# DDL_demo_board.net
KiCad netlist of a schematic drawn in EAGLE
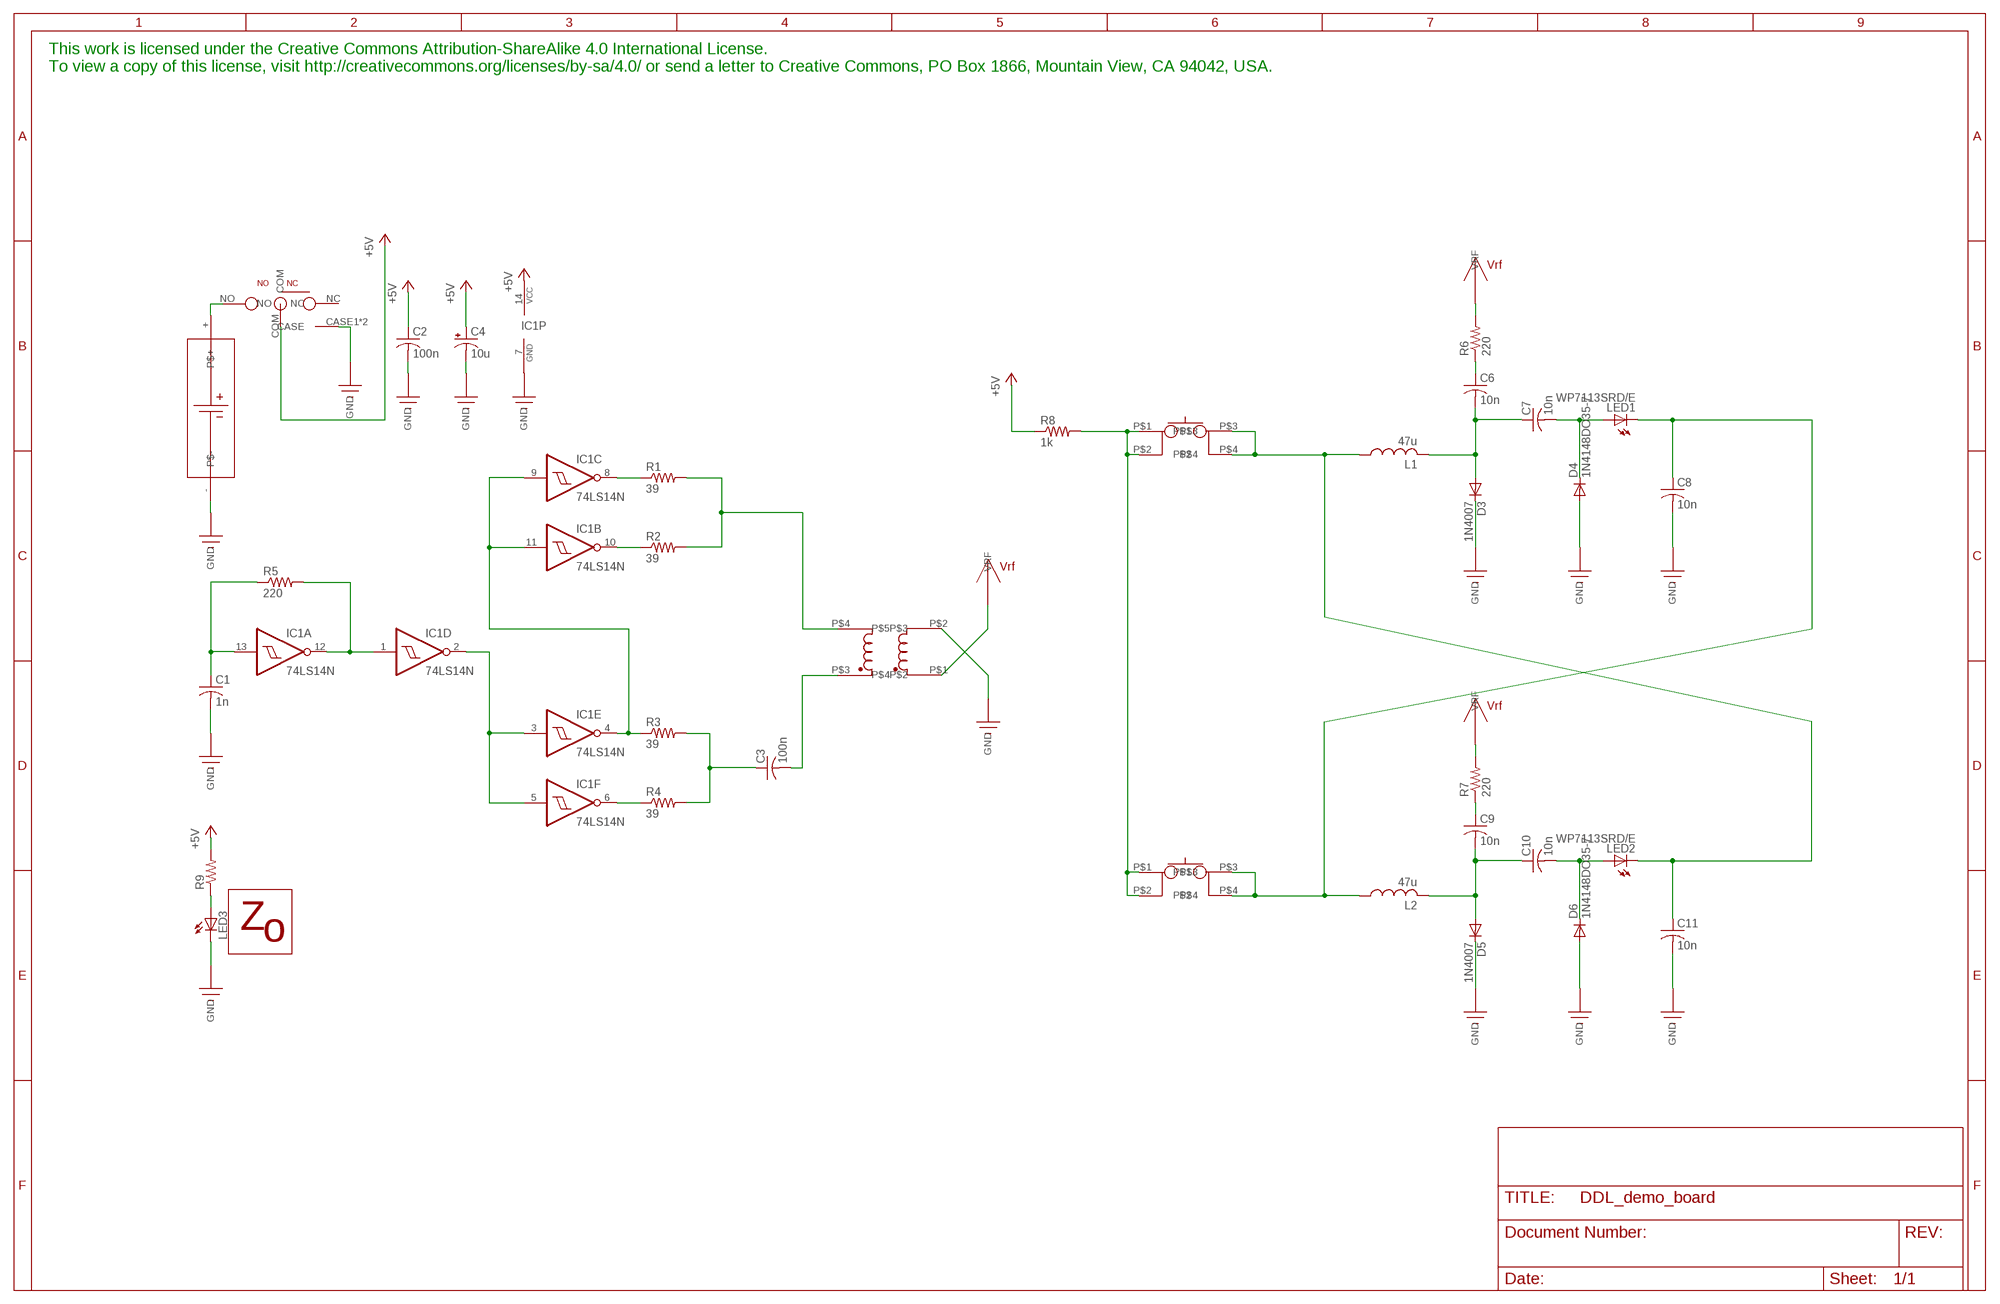
[diagram p0: schematic, sheet 1]

(export (version "E")
  (design (tool "Eeschema 10.0.6"))
  (components
    (comp (ref "C1")
      (value "1n")
      (footprint "eagle-import:C025-025X050")
      (libsource (lib "eagle-import") (part "C-US025-025X050"))
    )
    (comp (ref "C2")
      (value "100n")
      (footprint "eagle-import:C050-025X075")
      (libsource (lib "eagle-import") (part "C-US050-025X075"))
    )
    (comp (ref "C3")
      (value "100n")
      (footprint "eagle-import:C050-025X075")
      (libsource (lib "eagle-import") (part "C-US050-025X075"))
    )
    (comp (ref "C4")
      (value "10u")
      (footprint "eagle-import:E2,5-6")
      (libsource (lib "eagle-import") (part "CPOL-USE2.5-6"))
    )
    (comp (ref "C6")
      (value "10n")
      (footprint "eagle-import:C025-025X050")
      (libsource (lib "eagle-import") (part "C-US025-025X050"))
    )
    (comp (ref "C7")
      (value "10n")
      (footprint "eagle-import:C025-025X050")
      (libsource (lib "eagle-import") (part "C-US025-025X050"))
    )
    (comp (ref "C8")
      (value "10n")
      (footprint "eagle-import:C025-025X050")
      (libsource (lib "eagle-import") (part "C-US025-025X050"))
    )
    (comp (ref "C9")
      (value "10n")
      (footprint "eagle-import:C025-025X050")
      (libsource (lib "eagle-import") (part "C-US025-025X050"))
    )
    (comp (ref "C10")
      (value "10n")
      (footprint "eagle-import:C025-025X050")
      (libsource (lib "eagle-import") (part "C-US025-025X050"))
    )
    (comp (ref "C11")
      (value "10n")
      (footprint "eagle-import:C025-025X050")
      (libsource (lib "eagle-import") (part "C-US025-025X050"))
    )
    (comp (ref "D3")
      (value "1N4007")
      (footprint "eagle-import:DO41-10")
      (libsource (lib "eagle-import") (part "1N4007"))
    )
    (comp (ref "D4")
      (value "1N4148DO35-7")
      (footprint "eagle-import:DO35-7")
      (libsource (lib "eagle-import") (part "1N4148DO35-7"))
    )
    (comp (ref "D5")
      (value "1N4007")
      (footprint "eagle-import:DO41-10")
      (libsource (lib "eagle-import") (part "1N4007"))
    )
    (comp (ref "D6")
      (value "1N4148DO35-7")
      (footprint "eagle-import:DO35-7")
      (libsource (lib "eagle-import") (part "1N4148DO35-7"))
    )
    (comp (ref "IC1")
      (value "74LS14N")
      (footprint "eagle-import:DIL14")
      (libsource (lib "eagle-import") (part "7414NLS"))
    )
    (comp (ref "L1")
      (value "47u")
      (footprint "eagle-import:0207_10")
      (libsource (lib "eagle-import") (part "L-US0207/10"))
    )
    (comp (ref "L2")
      (value "47u")
      (footprint "eagle-import:0207_10")
      (libsource (lib "eagle-import") (part "L-US0207/10"))
    )
    (comp (ref "LED1")
      (value "WP7113SRD/E")
      (footprint "eagle-import:LED5MM")
      (libsource (lib "eagle-import") (part "LED5MM"))
    )
    (comp (ref "LED2")
      (value "WP7113SRD/E")
      (footprint "eagle-import:LED5MM")
      (libsource (lib "eagle-import") (part "LED5MM"))
    )
    (comp (ref "LED3")
      (value "LEDP-LCC-2-BACK")
      (footprint "eagle-import:P-LCC-2-TOPLED-RG")
      (libsource (lib "eagle-import") (part "LEDP-LCC-2-BACK"))
    )
    (comp (ref "R1")
      (value "39")
      (footprint "eagle-import:0207_10")
      (libsource (lib "eagle-import") (part "R-US_0207/10"))
    )
    (comp (ref "R2")
      (value "39")
      (footprint "eagle-import:0207_10")
      (libsource (lib "eagle-import") (part "R-US_0207/10"))
    )
    (comp (ref "R3")
      (value "39")
      (footprint "eagle-import:0207_10")
      (libsource (lib "eagle-import") (part "R-US_0207/10"))
    )
    (comp (ref "R4")
      (value "39")
      (footprint "eagle-import:0207_10")
      (libsource (lib "eagle-import") (part "R-US_0207/10"))
    )
    (comp (ref "R5")
      (value "220")
      (footprint "eagle-import:0207_10")
      (libsource (lib "eagle-import") (part "R-US_0207/10"))
    )
    (comp (ref "R6")
      (value "220")
      (footprint "eagle-import:0207_10")
      (libsource (lib "eagle-import") (part "R-US_0207/10"))
    )
    (comp (ref "R7")
      (value "220")
      (footprint "eagle-import:0207_10")
      (libsource (lib "eagle-import") (part "R-US_0207/10"))
    )
    (comp (ref "R8")
      (value "1k")
      (footprint "eagle-import:0207_10")
      (libsource (lib "eagle-import") (part "R-US_0207/10"))
    )
    (comp (ref "R9")
      (value "R-US_R0805")
      (footprint "eagle-import:R0805")
      (libsource (lib "eagle-import") (part "R-US_R0805"))
    )
    (comp (ref "U$1")
      (value "Z0_LOGO200MIL_NS")
      (footprint "eagle-import:Z0_LOGO_200_MIL_NO_SILK")
      (libsource (lib "eagle-import") (part "Z0_LOGO200MIL_NS"))
    )
    (comp (ref "U$2")
      (value "OS1020_SPDT")
      (footprint "eagle-import:OS1020_SWITCH")
      (libsource (lib "eagle-import") (part "OS1020_SPDT"))
    )
    (comp (ref "U$10")
      (value "PCB_MOM_SPST_SWITCH")
      (footprint "eagle-import:SWITCH_PCB_MOM")
      (libsource (lib "eagle-import") (part "PCB_MOM_SPST_SWITCH"))
    )
    (comp (ref "U$11")
      (value "PCB_MOM_SPST_SWITCH")
      (footprint "eagle-import:SWITCH_PCB_MOM")
      (libsource (lib "eagle-import") (part "PCB_MOM_SPST_SWITCH"))
    )
    (comp (ref "U$12")
      (value "FT37_BIFILAR_1")
      (footprint "eagle-import:FT37_BIFILAR_VERT2")
      (libsource (lib "eagle-import") (part "FT37_BIFILAR_1"))
    )
    (comp (ref "U$16")
      (value "4AA_BATT_HOLDERNO_HOLES")
      (footprint "eagle-import:4AA_BATT_PACK_NO_HOLES")
      (libsource (lib "eagle-import") (part "4AA_BATT_HOLDERNO_HOLES"))
    )
  )
  (nets
    (net (code "1") (name "+5V") (class "Default")
      (node (ref "C2") (pin "1") (pinfunction "1_1") (pintype "passive"))
      (node (ref "C4") (pin "+") (pinfunction "+_+") (pintype "passive"))
      (node (ref "IC1") (pin "14") (pinfunction "VCC_14") (pintype "power_in"))
      (node (ref "R8") (pin "1") (pinfunction "1_1") (pintype "passive"))
      (node (ref "R9") (pin "2") (pinfunction "2_2") (pintype "passive"))
      (node (ref "U$2") (pin "COM") (pinfunction "COM_COM") (pintype "bidirectional"))
    )
    (net (code "2") (name "GND") (class "Default")
      (node (ref "C1") (pin "2") (pinfunction "2_2") (pintype "passive"))
      (node (ref "C11") (pin "2") (pinfunction "2_2") (pintype "passive"))
      (node (ref "C2") (pin "2") (pinfunction "2_2") (pintype "passive"))
      (node (ref "C4") (pin "-") (pinfunction "-_-") (pintype "passive"))
      (node (ref "C8") (pin "2") (pinfunction "2_2") (pintype "passive"))
      (node (ref "D3") (pin "C") (pinfunction "C_C") (pintype "passive"))
      (node (ref "D4") (pin "A") (pinfunction "A_A") (pintype "passive"))
      (node (ref "D5") (pin "C") (pinfunction "C_C") (pintype "passive"))
      (node (ref "D6") (pin "A") (pinfunction "A_A") (pintype "passive"))
      (node (ref "IC1") (pin "7") (pinfunction "GND_7") (pintype "power_in"))
      (node (ref "LED3") (pin "C") (pinfunction "C_C") (pintype "passive"))
      (node (ref "U$12") (pin "P$2") (pinfunction "P$3_P$2") (pintype "bidirectional"))
      (node (ref "U$16") (pin "-") (pinfunction "P$-_-") (pintype "bidirectional"))
      (node (ref "U$2") (pin "CASE1") (pinfunction "CASE_CASE1") (pintype "bidirectional"))
      (node (ref "U$2") (pin "CASE2") (pinfunction "CASE_CASE2") (pintype "bidirectional"))
    )
    (net (code "3") (name "Net-(C3-Pad1)") (class "Default")
      (node (ref "C3") (pin "1") (pinfunction "1_1") (pintype "passive"))
      (node (ref "R3") (pin "2") (pinfunction "2_2") (pintype "passive"))
      (node (ref "R4") (pin "2") (pinfunction "2_2") (pintype "passive"))
    )
    (net (code "4") (name "Net-(C6-Pad1)") (class "Default")
      (node (ref "C6") (pin "1") (pinfunction "1_1") (pintype "passive"))
      (node (ref "R6") (pin "1") (pinfunction "1_1") (pintype "passive"))
    )
    (net (code "5") (name "Net-(C6-Pad2)") (class "Default")
      (node (ref "C6") (pin "2") (pinfunction "2_2") (pintype "passive"))
      (node (ref "C7") (pin "1") (pinfunction "1_1") (pintype "passive"))
      (node (ref "D3") (pin "A") (pinfunction "A_A") (pintype "passive"))
      (node (ref "L1") (pin "2") (pinfunction "2_2") (pintype "passive"))
    )
    (net (code "6") (name "Net-(C7-Pad2)") (class "Default")
      (node (ref "C7") (pin "2") (pinfunction "2_2") (pintype "passive"))
      (node (ref "D4") (pin "C") (pinfunction "C_C") (pintype "passive"))
      (node (ref "LED1") (pin "A") (pinfunction "A_A") (pintype "passive"))
    )
    (net (code "7") (name "Net-(C9-Pad1)") (class "Default")
      (node (ref "C9") (pin "1") (pinfunction "1_1") (pintype "passive"))
      (node (ref "R7") (pin "1") (pinfunction "1_1") (pintype "passive"))
    )
    (net (code "8") (name "Net-(C10-Pad1)") (class "Default")
      (node (ref "C10") (pin "1") (pinfunction "1_1") (pintype "passive"))
      (node (ref "C9") (pin "2") (pinfunction "2_2") (pintype "passive"))
      (node (ref "D5") (pin "A") (pinfunction "A_A") (pintype "passive"))
      (node (ref "L2") (pin "2") (pinfunction "2_2") (pintype "passive"))
    )
    (net (code "9") (name "Net-(C10-Pad2)") (class "Default")
      (node (ref "C10") (pin "2") (pinfunction "2_2") (pintype "passive"))
      (node (ref "D6") (pin "C") (pinfunction "C_C") (pintype "passive"))
      (node (ref "LED2") (pin "A") (pinfunction "A_A") (pintype "passive"))
    )
    (net (code "10") (name "Net-(IC1A-I)") (class "Default")
      (node (ref "C1") (pin "1") (pinfunction "1_1") (pintype "passive"))
      (node (ref "IC1") (pin "13") (pinfunction "I_13") (pintype "input"))
      (node (ref "R5") (pin "1") (pinfunction "1_1") (pintype "passive"))
    )
    (net (code "11") (name "Net-(IC1A-O)") (class "Default")
      (node (ref "IC1") (pin "1") (pinfunction "I_1") (pintype "input"))
      (node (ref "IC1") (pin "12") (pinfunction "O_12") (pintype "output"))
      (node (ref "R5") (pin "2") (pinfunction "2_2") (pintype "passive"))
    )
    (net (code "12") (name "Net-(IC1B-I)") (class "Default")
      (node (ref "IC1") (pin "11") (pinfunction "I_11") (pintype "input"))
      (node (ref "IC1") (pin "4") (pinfunction "O_4") (pintype "output"))
      (node (ref "IC1") (pin "9") (pinfunction "I_9") (pintype "input"))
      (node (ref "R3") (pin "1") (pinfunction "1_1") (pintype "passive"))
    )
    (net (code "13") (name "Net-(IC1B-O)") (class "Default")
      (node (ref "IC1") (pin "10") (pinfunction "O_10") (pintype "output"))
      (node (ref "R2") (pin "1") (pinfunction "1_1") (pintype "passive"))
    )
    (net (code "14") (name "Net-(IC1C-O)") (class "Default")
      (node (ref "IC1") (pin "8") (pinfunction "O_8") (pintype "output"))
      (node (ref "R1") (pin "1") (pinfunction "1_1") (pintype "passive"))
    )
    (net (code "15") (name "Net-(IC1D-O)") (class "Default")
      (node (ref "IC1") (pin "2") (pinfunction "O_2") (pintype "output"))
      (node (ref "IC1") (pin "3") (pinfunction "I_3") (pintype "input"))
      (node (ref "IC1") (pin "5") (pinfunction "I_5") (pintype "input"))
    )
    (net (code "16") (name "Net-(IC1F-O)") (class "Default")
      (node (ref "IC1") (pin "6") (pinfunction "O_6") (pintype "output"))
      (node (ref "R4") (pin "1") (pinfunction "1_1") (pintype "passive"))
    )
    (net (code "17") (name "Net-(LED1-C)") (class "Default")
      (node (ref "C8") (pin "1") (pinfunction "1_1") (pintype "passive"))
      (node (ref "L2") (pin "1") (pinfunction "1_1") (pintype "passive"))
      (node (ref "LED1") (pin "K") (pinfunction "C_K") (pintype "passive"))
      (node (ref "U$11") (pin "P$3") (pinfunction "P$3_P$3") (pintype "bidirectional"))
      (node (ref "U$11") (pin "P$4") (pinfunction "P$4_P$4") (pintype "bidirectional"))
    )
    (net (code "18") (name "Net-(LED2-C)") (class "Default")
      (node (ref "C11") (pin "1") (pinfunction "1_1") (pintype "passive"))
      (node (ref "L1") (pin "1") (pinfunction "1_1") (pintype "passive"))
      (node (ref "LED2") (pin "K") (pinfunction "C_K") (pintype "passive"))
      (node (ref "U$10") (pin "P$3") (pinfunction "P$3_P$3") (pintype "bidirectional"))
      (node (ref "U$10") (pin "P$4") (pinfunction "P$4_P$4") (pintype "bidirectional"))
    )
    (net (code "19") (name "Net-(LED3-PadA)") (class "Default")
      (node (ref "LED3") (pin "A") (pinfunction "A_A") (pintype "passive"))
      (node (ref "R9") (pin "1") (pinfunction "1_1") (pintype "passive"))
    )
    (net (code "20") (name "Net-(R8-Pad2)") (class "Default")
      (node (ref "R8") (pin "2") (pinfunction "2_2") (pintype "passive"))
      (node (ref "U$10") (pin "P$1") (pinfunction "P$1_P$1") (pintype "bidirectional"))
      (node (ref "U$10") (pin "P$2") (pinfunction "P$2_P$2") (pintype "bidirectional"))
      (node (ref "U$11") (pin "P$1") (pinfunction "P$1_P$1") (pintype "bidirectional"))
      (node (ref "U$11") (pin "P$2") (pinfunction "P$2_P$2") (pintype "bidirectional"))
    )
    (net (code "21") (name "Net-(U$12-P$4)") (class "Default")
      (node (ref "C3") (pin "2") (pinfunction "2_2") (pintype "passive"))
      (node (ref "U$12") (pin "P$3") (pinfunction "P$4_P$3") (pintype "bidirectional"))
    )
    (net (code "22") (name "Net-(U$12-P$5)") (class "Default")
      (node (ref "R1") (pin "2") (pinfunction "2_2") (pintype "passive"))
      (node (ref "R2") (pin "2") (pinfunction "2_2") (pintype "passive"))
      (node (ref "U$12") (pin "P$4") (pinfunction "P$5_P$4") (pintype "bidirectional"))
    )
    (net (code "23") (name "Net-(U$16-P$+)") (class "Default")
      (node (ref "U$16") (pin "+") (pinfunction "P$+_+") (pintype "bidirectional"))
      (node (ref "U$2") (pin "NO") (pinfunction "NO_NO") (pintype "bidirectional"))
    )
    (net (code "24") (name "V_RF") (class "Default")
      (node (ref "R6") (pin "2") (pinfunction "2_2") (pintype "passive"))
      (node (ref "R7") (pin "2") (pinfunction "2_2") (pintype "passive"))
      (node (ref "U$12") (pin "P$1") (pinfunction "P$2_P$1") (pintype "bidirectional"))
    )
    (net (code "25") (name "unconnected-(U$2-PadNC)") (class "Default")
      (node (ref "U$2") (pin "NC") (pinfunction "NC_NC") (pintype "bidirectional"))
    )
  )
)
